# Decawave.net
KiCad netlist of a schematic drawn in Altium Designer
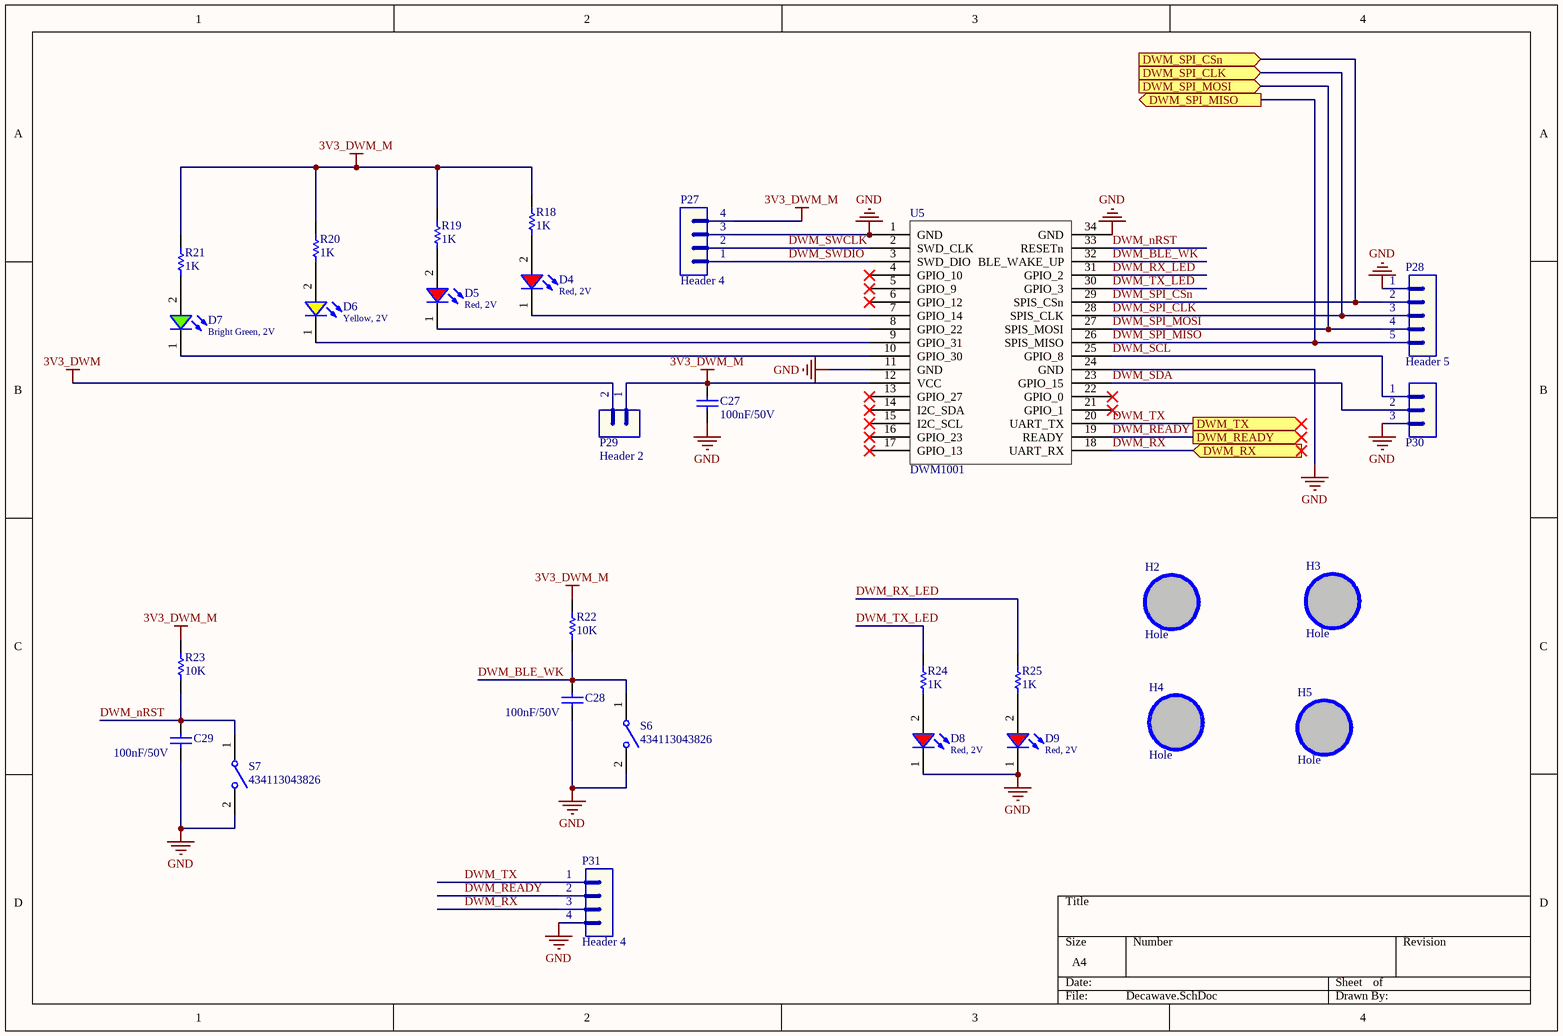
[diagram p0: Decawave.SchDoc]

(export (version "E")
  (design (tool "Eeschema 10.0.6"))
  (components
    (comp (ref "C27")
      (value "100nF/50V")
      (footprint "CAP-SM-0805")
      (description "CAP CER 0.1UF 50V Y5V 0805")
      (fields
        (field (name "MANUFACTURER") "Samsung Electro-Mechanics")
        (field (name "MANUFACTURER PART NUMBER") "CL21F104ZBCNNNC")
      )
      (libsource (lib "Capacitor") (part "Cap-100nF-50V-0805"))
    )
    (comp (ref "C28")
      (value "100nF/50V")
      (footprint "CAP-SM-0805")
      (description "CAP CER 0.1UF 50V Y5V 0805")
      (fields
        (field (name "MANUFACTURER") "Samsung Electro-Mechanics")
        (field (name "MANUFACTURER PART NUMBER") "CL21F104ZBCNNNC")
      )
      (libsource (lib "Capacitor") (part "Cap-100nF-50V-0805"))
    )
    (comp (ref "C29")
      (value "100nF/50V")
      (footprint "CAP-SM-0805")
      (description "CAP CER 0.1UF 50V Y5V 0805")
      (fields
        (field (name "MANUFACTURER") "Samsung Electro-Mechanics")
        (field (name "MANUFACTURER PART NUMBER") "CL21F104ZBCNNNC")
      )
      (libsource (lib "Capacitor") (part "Cap-100nF-50V-0805"))
    )
    (comp (ref "D4")
      (value "Red, 2V")
      (footprint "WL-SMCW_0805")
      (description "WL-SMCW SMT Mono-color Chip LED Waterclear, size 0805, Red, 2V, 140deg")
      (fields (field (name "PART NUMBER") "150080RS75000") (field (name "PUBLISHER") "Wurth Elektronik"))
      (libsource (lib "LED_GREEN") (part "150080RS75000"))
    )
    (comp (ref "D5")
      (value "Red, 2V")
      (footprint "WL-SMCW_0805")
      (description "WL-SMCW SMT Mono-color Chip LED Waterclear, size 0805, Red, 2V, 140deg")
      (fields (field (name "PART NUMBER") "150080RS75000") (field (name "PUBLISHER") "Wurth Elektronik"))
      (libsource (lib "LED_GREEN") (part "150080RS75000"))
    )
    (comp (ref "D6")
      (value "Yellow, 2V")
      (footprint "WL-SMCW_0805")
      (description "WL-SMCW SMT Mono-color Chip LED Waterclear, size 0805, Yellow, 2V, 140deg")
      (fields (field (name "PART NUMBER") "150080YS75000") (field (name "PUBLISHER") "Wurth Elektronik"))
      (libsource (lib "LED_GREEN") (part "150080YS75000"))
    )
    (comp (ref "D7")
      (value "Bright Green, 2V")
      (footprint "WL-SMCW_0805")
      (description "WL-SMCW SMT Mono-color Chip LED Waterclear, size 0805, Bright Green, 2V, 140deg")
      (fields (field (name "PART NUMBER") "150080VS75000") (field (name "PUBLISHER") "Wurth Elektronik"))
      (libsource (lib "LED_GREEN") (part "150080VS75000"))
    )
    (comp (ref "D8")
      (value "Red, 2V")
      (footprint "WL-SMCW_0805")
      (description "WL-SMCW SMT Mono-color Chip LED Waterclear, size 0805, Red, 2V, 140deg")
      (fields (field (name "PART NUMBER") "150080RS75000") (field (name "PUBLISHER") "Wurth Elektronik"))
      (libsource (lib "LED_GREEN") (part "150080RS75000"))
    )
    (comp (ref "D9")
      (value "Red, 2V")
      (footprint "WL-SMCW_0805")
      (description "WL-SMCW SMT Mono-color Chip LED Waterclear, size 0805, Red, 2V, 140deg")
      (fields (field (name "PART NUMBER") "150080RS75000") (field (name "PUBLISHER") "Wurth Elektronik"))
      (libsource (lib "LED_GREEN") (part "150080RS75000"))
    )
    (comp (ref "H2")
      (value "Hole")
      (footprint "LO KHOAN 3MM")
      (description "Hole 3mm")
      (libsource (lib "PIF_C16_lib") (part "Hole"))
    )
    (comp (ref "H3")
      (value "Hole")
      (footprint "LO KHOAN 3MM")
      (description "Hole 3mm")
      (libsource (lib "PIF_C16_lib") (part "Hole"))
    )
    (comp (ref "H4")
      (value "Hole")
      (footprint "LO KHOAN 3MM")
      (description "Hole 3mm")
      (libsource (lib "PIF_C16_lib") (part "Hole"))
    )
    (comp (ref "H5")
      (value "Hole")
      (footprint "LO KHOAN 3MM")
      (description "Hole 3mm")
      (libsource (lib "PIF_C16_lib") (part "Hole"))
    )
    (comp (ref "P27")
      (value "Header 4")
      (footprint "JP4")
      (description "Header, 4-Pin")
      (fields (field (name "PUBLISHER") "Altium Limited"))
      (libsource (lib "Header-connector") (part "Header 4"))
    )
    (comp (ref "P28")
      (value "Header 5")
      (footprint "JP5")
      (description "Header, 5-Pin")
      (fields (field (name "PUBLISHER") "Altium Limited"))
      (libsource (lib "Header-connector") (part "Header 5"))
    )
    (comp (ref "P29")
      (value "Header 2")
      (footprint "JP2")
      (description "Header, 2-Pin")
      (fields (field (name "PUBLISHER") "Altium Limited"))
      (libsource (lib "Header-connector") (part "Header 2"))
    )
    (comp (ref "P30")
      (value "Header 3")
      (footprint "JP3")
      (description "Header, 3-Pin")
      (fields (field (name "PUBLISHER") "Altium Limited"))
      (libsource (lib "Header-connector") (part "Header 3"))
    )
    (comp (ref "P31")
      (value "Header 4")
      (footprint "JP4")
      (description "Header, 4-Pin")
      (fields (field (name "PUBLISHER") "Altium Limited"))
      (libsource (lib "") (part "Header 4_1"))
    )
    (comp (ref "R18")
      (value "1K")
      (footprint "Resistor:RES-SM-0805")
      (description "RES 1K OHM 1% 1/4W 0805")
      (fields
        (field (name "MANUFACTURER") "Stackpole Electronics Inc")
        (field (name "MANUFACTURER PART NUMBER") "RNCP0805FTD1K00")
      )
      (libsource (lib "Resistor") (part "Res-1K-0805"))
    )
    (comp (ref "R19")
      (value "1K")
      (footprint "Resistor:RES-SM-0805")
      (description "RES 1K OHM 1% 1/4W 0805")
      (fields
        (field (name "MANUFACTURER") "Stackpole Electronics Inc")
        (field (name "MANUFACTURER PART NUMBER") "RNCP0805FTD1K00")
      )
      (libsource (lib "Resistor") (part "Res-1K-0805"))
    )
    (comp (ref "R20")
      (value "1K")
      (footprint "Resistor:RES-SM-0805")
      (description "RES 1K OHM 1% 1/4W 0805")
      (fields
        (field (name "MANUFACTURER") "Stackpole Electronics Inc")
        (field (name "MANUFACTURER PART NUMBER") "RNCP0805FTD1K00")
      )
      (libsource (lib "Resistor") (part "Res-1K-0805"))
    )
    (comp (ref "R21")
      (value "1K")
      (footprint "Resistor:RES-SM-0805")
      (description "RES 1K OHM 1% 1/4W 0805")
      (fields
        (field (name "MANUFACTURER") "Stackpole Electronics Inc")
        (field (name "MANUFACTURER PART NUMBER") "RNCP0805FTD1K00")
      )
      (libsource (lib "Resistor") (part "Res-1K-0805"))
    )
    (comp (ref "R22")
      (value "10K")
      (footprint "Resistor:RES-SM-0805")
      (description "RES 10K OHM 1% 1/4W 0805")
      (fields
        (field (name "MANUFACTURER") "Stackpole Electronics Inc")
        (field (name "MANUFACTURER PART NUMBER") "RNCP0805FTD10K0")
      )
      (libsource (lib "Resistor") (part "Res-10k-0805"))
    )
    (comp (ref "R23")
      (value "10K")
      (footprint "Resistor:RES-SM-0805")
      (description "RES 10K OHM 1% 1/4W 0805")
      (fields
        (field (name "MANUFACTURER") "Stackpole Electronics Inc")
        (field (name "MANUFACTURER PART NUMBER") "RNCP0805FTD10K0")
      )
      (libsource (lib "Resistor") (part "Res-10k-0805"))
    )
    (comp (ref "R24")
      (value "1K")
      (footprint "Resistor:RES-SM-0805")
      (description "RES 1K OHM 1% 1/4W 0805")
      (fields
        (field (name "MANUFACTURER") "Stackpole Electronics Inc")
        (field (name "MANUFACTURER PART NUMBER") "RNCP0805FTD1K00")
      )
      (libsource (lib "Resistor") (part "Res-1K-0805"))
    )
    (comp (ref "R25")
      (value "1K")
      (footprint "Resistor:RES-SM-0805")
      (description "RES 1K OHM 1% 1/4W 0805")
      (fields
        (field (name "MANUFACTURER") "Stackpole Electronics Inc")
        (field (name "MANUFACTURER PART NUMBER") "RNCP0805FTD1K00")
      )
      (libsource (lib "Resistor") (part "Res-1K-0805"))
    )
    (comp (ref "S6")
      (value "434113043826")
      (footprint "434113043826")
      (description "WS-TASV J-Bend SMT Tact Switch 6x3.5mm, height 4.3mm, 260gf")
      (fields (field (name "PUBLISHER") "Wurth Elektronik"))
      (libsource (lib "434123043816") (part "434113043826"))
    )
    (comp (ref "S7")
      (value "434113043826")
      (footprint "434113043826")
      (description "WS-TASV J-Bend SMT Tact Switch 6x3.5mm, height 4.3mm, 260gf")
      (fields (field (name "PUBLISHER") "Wurth Elektronik"))
      (libsource (lib "434123043816") (part "434113043826"))
    )
    (comp (ref "U5") (value "DWM1001") (footprint "DWM1001") (libsource (lib "xecanbang") (part "DWM1001")))
  )
  (nets
    (net (code "1") (name "/DWM_BLE_WK") (class "Default")
      (node (ref "C28") (pin "2") (pinfunction "2_2") (pintype "passive"))
      (node (ref "R22") (pin "1") (pinfunction "1_1") (pintype "passive"))
      (node (ref "S6") (pin "1") (pinfunction "1_1") (pintype "passive"))
      (node (ref "U5") (pin "32") (pinfunction "BLE_WAKE_UP_32") (pintype "passive"))
    )
    (net (code "2") (name "/DWM_READY") (class "Default")
      (node (ref "P31") (pin "2") (pinfunction "2_2") (pintype "passive"))
      (node (ref "U5") (pin "19") (pinfunction "READY_19") (pintype "passive"))
    )
    (net (code "3") (name "/DWM_RX") (class "Default")
      (node (ref "P31") (pin "3") (pinfunction "3_3") (pintype "passive"))
      (node (ref "U5") (pin "18") (pinfunction "UART_RX_18") (pintype "passive"))
    )
    (net (code "4") (name "/DWM_RX_LED") (class "Default")
      (node (ref "R25") (pin "2") (pinfunction "2_2") (pintype "passive"))
      (node (ref "U5") (pin "31") (pinfunction "GPIO_2_31") (pintype "passive"))
    )
    (net (code "5") (name "/DWM_SCL") (class "Default")
      (node (ref "P30") (pin "1") (pinfunction "1_1") (pintype "passive"))
      (node (ref "U5") (pin "25") (pinfunction "GPIO_8_25") (pintype "passive"))
    )
    (net (code "6") (name "/DWM_SDA") (class "Default")
      (node (ref "P30") (pin "2") (pinfunction "2_2") (pintype "passive"))
      (node (ref "U5") (pin "23") (pinfunction "GPIO_15_23") (pintype "passive"))
    )
    (net (code "7") (name "/DWM_SPI_CLK") (class "Default")
      (node (ref "P28") (pin "3") (pinfunction "3_3") (pintype "passive"))
      (node (ref "U5") (pin "28") (pinfunction "SPIS_CLK_28") (pintype "passive"))
    )
    (net (code "8") (name "/DWM_SPI_CSn") (class "Default")
      (node (ref "P28") (pin "2") (pinfunction "2_2") (pintype "passive"))
      (node (ref "U5") (pin "29") (pinfunction "SPIS_CSn_29") (pintype "passive"))
    )
    (net (code "9") (name "/DWM_SPI_MISO") (class "Default")
      (node (ref "P28") (pin "5") (pinfunction "5_5") (pintype "passive"))
      (node (ref "U5") (pin "26") (pinfunction "SPIS_MISO_26") (pintype "passive"))
    )
    (net (code "10") (name "/DWM_SPI_MOSI") (class "Default")
      (node (ref "P28") (pin "4") (pinfunction "4_4") (pintype "passive"))
      (node (ref "U5") (pin "27") (pinfunction "SPIS_MOSI_27") (pintype "passive"))
    )
    (net (code "11") (name "/DWM_SWCLK") (class "Default")
      (node (ref "P27") (pin "2") (pinfunction "2_2") (pintype "passive"))
      (node (ref "U5") (pin "2") (pinfunction "SWD_CLK_2") (pintype "passive"))
    )
    (net (code "12") (name "/DWM_SWDIO") (class "Default")
      (node (ref "P27") (pin "1") (pinfunction "1_1") (pintype "passive"))
      (node (ref "U5") (pin "3") (pinfunction "SWD_DIO_3") (pintype "passive"))
    )
    (net (code "13") (name "/DWM_TX") (class "Default")
      (node (ref "P31") (pin "1") (pinfunction "1_1") (pintype "passive"))
      (node (ref "U5") (pin "20") (pinfunction "UART_TX_20") (pintype "passive"))
    )
    (net (code "14") (name "/DWM_TX_LED") (class "Default")
      (node (ref "R24") (pin "2") (pinfunction "2_2") (pintype "passive"))
      (node (ref "U5") (pin "30") (pinfunction "GPIO_3_30") (pintype "passive"))
    )
    (net (code "15") (name "/DWM_nRST") (class "Default")
      (node (ref "C29") (pin "2") (pinfunction "2_2") (pintype "passive"))
      (node (ref "R23") (pin "1") (pinfunction "1_1") (pintype "passive"))
      (node (ref "S7") (pin "1") (pinfunction "1_1") (pintype "passive"))
      (node (ref "U5") (pin "33") (pinfunction "RESETn_33") (pintype "passive"))
    )
    (net (code "16") (name "3V3_DWM") (class "Default")
      (node (ref "P29") (pin "2") (pinfunction "2_2") (pintype "passive"))
    )
    (net (code "17") (name "3V3_DWM_M") (class "Default")
      (node (ref "C27") (pin "2") (pinfunction "2_2") (pintype "passive"))
      (node (ref "P27") (pin "4") (pinfunction "4_4") (pintype "passive"))
      (node (ref "P29") (pin "1") (pinfunction "1_1") (pintype "passive"))
      (node (ref "R18") (pin "2") (pinfunction "2_2") (pintype "passive"))
      (node (ref "R19") (pin "2") (pinfunction "2_2") (pintype "passive"))
      (node (ref "R20") (pin "2") (pinfunction "2_2") (pintype "passive"))
      (node (ref "R21") (pin "2") (pinfunction "2_2") (pintype "passive"))
      (node (ref "R22") (pin "2") (pinfunction "2_2") (pintype "passive"))
      (node (ref "R23") (pin "2") (pinfunction "2_2") (pintype "passive"))
      (node (ref "U5") (pin "12") (pinfunction "VCC_12") (pintype "passive"))
    )
    (net (code "18") (name "GND") (class "Default")
      (node (ref "C27") (pin "1") (pinfunction "1_1") (pintype "passive"))
      (node (ref "C28") (pin "1") (pinfunction "1_1") (pintype "passive"))
      (node (ref "C29") (pin "1") (pinfunction "1_1") (pintype "passive"))
      (node (ref "D8") (pin "1") (pinfunction "K_1") (pintype "passive"))
      (node (ref "D9") (pin "1") (pinfunction "K_1") (pintype "passive"))
      (node (ref "P27") (pin "3") (pinfunction "3_3") (pintype "passive"))
      (node (ref "P28") (pin "1") (pinfunction "1_1") (pintype "passive"))
      (node (ref "P30") (pin "3") (pinfunction "3_3") (pintype "passive"))
      (node (ref "P31") (pin "4") (pinfunction "4_4") (pintype "passive"))
      (node (ref "S6") (pin "2") (pinfunction "2_2") (pintype "passive"))
      (node (ref "S7") (pin "2") (pinfunction "2_2") (pintype "passive"))
      (node (ref "U5") (pin "1") (pinfunction "GND_1") (pintype "passive"))
      (node (ref "U5") (pin "11") (pinfunction "GND_11") (pintype "passive"))
      (node (ref "U5") (pin "24") (pinfunction "GND_24") (pintype "passive"))
      (node (ref "U5") (pin "34") (pinfunction "GND_34") (pintype "passive"))
    )
    (net (code "19") (name "Net-(D4-A)") (class "Default")
      (node (ref "D4") (pin "2") (pinfunction "A_2") (pintype "passive"))
      (node (ref "R18") (pin "1") (pinfunction "1_1") (pintype "passive"))
    )
    (net (code "20") (name "Net-(D4-K)") (class "Default")
      (node (ref "D4") (pin "1") (pinfunction "K_1") (pintype "passive"))
      (node (ref "U5") (pin "7") (pinfunction "GPIO_14_7") (pintype "passive"))
    )
    (net (code "21") (name "Net-(D5-A)") (class "Default")
      (node (ref "D5") (pin "2") (pinfunction "A_2") (pintype "passive"))
      (node (ref "R19") (pin "1") (pinfunction "1_1") (pintype "passive"))
    )
    (net (code "22") (name "Net-(D5-K)") (class "Default")
      (node (ref "D5") (pin "1") (pinfunction "K_1") (pintype "passive"))
      (node (ref "U5") (pin "8") (pinfunction "GPIO_22_8") (pintype "passive"))
    )
    (net (code "23") (name "Net-(D6-A)") (class "Default")
      (node (ref "D6") (pin "2") (pinfunction "A_2") (pintype "passive"))
      (node (ref "R20") (pin "1") (pinfunction "1_1") (pintype "passive"))
    )
    (net (code "24") (name "Net-(D6-K)") (class "Default")
      (node (ref "D6") (pin "1") (pinfunction "K_1") (pintype "passive"))
      (node (ref "U5") (pin "9") (pinfunction "GPIO_31_9") (pintype "passive"))
    )
    (net (code "25") (name "Net-(D7-A)") (class "Default")
      (node (ref "D7") (pin "2") (pinfunction "A_2") (pintype "passive"))
      (node (ref "R21") (pin "1") (pinfunction "1_1") (pintype "passive"))
    )
    (net (code "26") (name "Net-(D7-K)") (class "Default")
      (node (ref "D7") (pin "1") (pinfunction "K_1") (pintype "passive"))
      (node (ref "U5") (pin "10") (pinfunction "GPIO_30_10") (pintype "passive"))
    )
    (net (code "27") (name "Net-(D8-A)") (class "Default")
      (node (ref "D8") (pin "2") (pinfunction "A_2") (pintype "passive"))
      (node (ref "R24") (pin "1") (pinfunction "1_1") (pintype "passive"))
    )
    (net (code "28") (name "Net-(D9-A)") (class "Default")
      (node (ref "D9") (pin "2") (pinfunction "A_2") (pintype "passive"))
      (node (ref "R25") (pin "1") (pinfunction "1_1") (pintype "passive"))
    )
    (net (code "29") (name "unconnected-(H2-Pad1)") (class "Default")
      (node (ref "H2") (pin "1") (pinfunction "1_1") (pintype "passive"))
    )
    (net (code "30") (name "unconnected-(H3-Pad1)") (class "Default")
      (node (ref "H3") (pin "1") (pinfunction "1_1") (pintype "passive"))
    )
    (net (code "31") (name "unconnected-(H4-Pad1)") (class "Default")
      (node (ref "H4") (pin "1") (pinfunction "1_1") (pintype "passive"))
    )
    (net (code "32") (name "unconnected-(H5-Pad1)") (class "Default")
      (node (ref "H5") (pin "1") (pinfunction "1_1") (pintype "passive"))
    )
    (net (code "33") (name "unconnected-(U5-GPIO_0-Pad22)") (class "Default")
      (node (ref "U5") (pin "22") (pinfunction "GPIO_0_22") (pintype "passive+no_connect"))
    )
    (net (code "34") (name "unconnected-(U5-GPIO_1-Pad21)") (class "Default")
      (node (ref "U5") (pin "21") (pinfunction "GPIO_1_21") (pintype "passive+no_connect"))
    )
    (net (code "35") (name "unconnected-(U5-GPIO_9-Pad5)") (class "Default")
      (node (ref "U5") (pin "5") (pinfunction "GPIO_9_5") (pintype "passive+no_connect"))
    )
    (net (code "36") (name "unconnected-(U5-GPIO_10-Pad4)") (class "Default")
      (node (ref "U5") (pin "4") (pinfunction "GPIO_10_4") (pintype "passive+no_connect"))
    )
    (net (code "37") (name "unconnected-(U5-GPIO_12-Pad6)") (class "Default")
      (node (ref "U5") (pin "6") (pinfunction "GPIO_12_6") (pintype "passive+no_connect"))
    )
    (net (code "38") (name "unconnected-(U5-GPIO_13-Pad17)") (class "Default")
      (node (ref "U5") (pin "17") (pinfunction "GPIO_13_17") (pintype "passive+no_connect"))
    )
    (net (code "39") (name "unconnected-(U5-GPIO_23-Pad16)") (class "Default")
      (node (ref "U5") (pin "16") (pinfunction "GPIO_23_16") (pintype "passive+no_connect"))
    )
    (net (code "40") (name "unconnected-(U5-GPIO_27-Pad13)") (class "Default")
      (node (ref "U5") (pin "13") (pinfunction "GPIO_27_13") (pintype "passive+no_connect"))
    )
    (net (code "41") (name "unconnected-(U5-I2C_SCL-Pad15)") (class "Default")
      (node (ref "U5") (pin "15") (pinfunction "I2C_SCL_15") (pintype "passive+no_connect"))
    )
    (net (code "42") (name "unconnected-(U5-I2C_SDA-Pad14)") (class "Default")
      (node (ref "U5") (pin "14") (pinfunction "I2C_SDA_14") (pintype "passive+no_connect"))
    )
  )
)
